# tempSensorCR2032.net
KiCad netlist of a schematic drawn in EAGLE
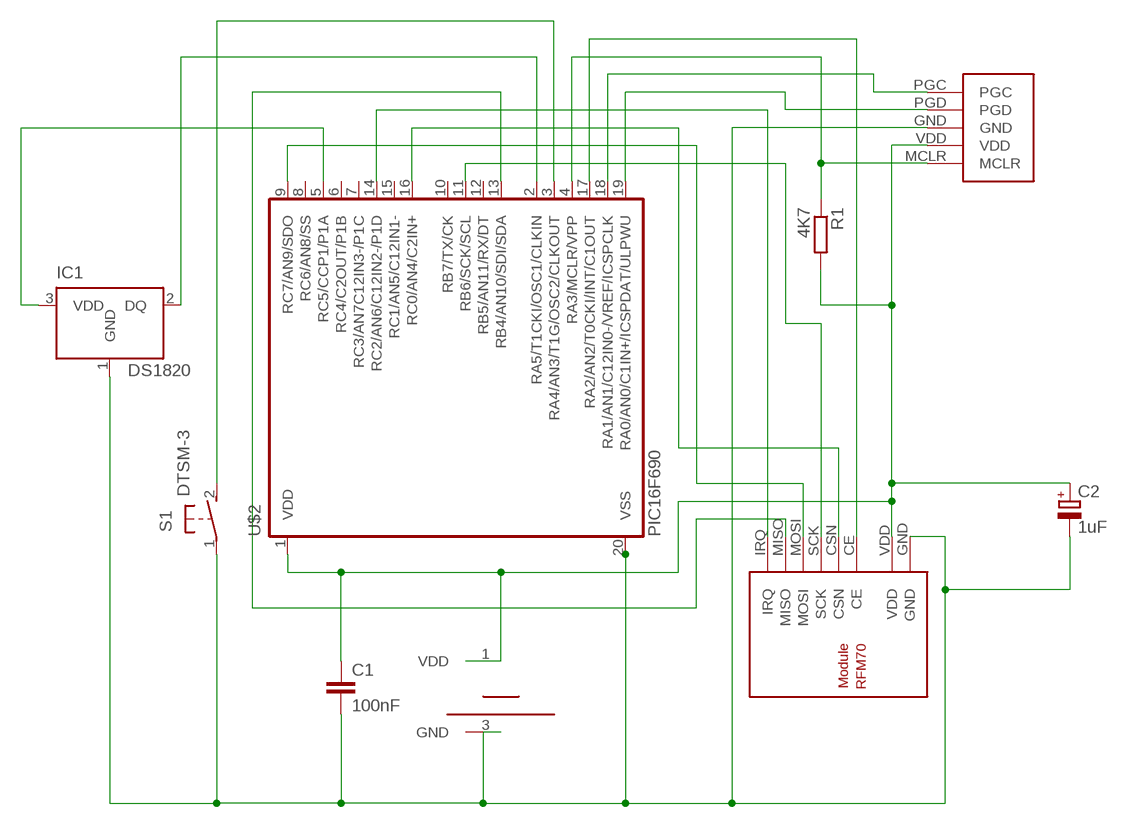
[diagram p0: schematic, sheet 1]

(export (version "E")
  (design (tool "Eeschema 10.0.6"))
  (components
    (comp (ref "C1")
      (value "100nF")
      (footprint "eagle-import:C2012")
      (libsource (lib "eagle-import") (part "C-EUC2012"))
    )
    (comp (ref "C2")
      (value "1uF")
      (footprint "eagle-import:SMC_A")
      (libsource (lib "eagle-import") (part "CPOL-EUSMCA"))
    )
    (comp (ref "IC1")
      (value "DS1820")
      (footprint "eagle-import:TO-92")
      (libsource (lib "eagle-import") (part "DS1820"))
    )
    (comp (ref "R1")
      (value "4K7")
      (footprint "eagle-import:R1206W")
      (libsource (lib "eagle-import") (part "R-EU_R1206W"))
    )
    (comp (ref "S1")
      (value "DTSM-3")
      (footprint "eagle-import:DTSM-3")
      (libsource (lib "eagle-import") (part "DTSM-3"))
    )
    (comp (ref "U$1")
      (value "RFM70")
      (footprint "eagle-import:RFM70")
      (libsource (lib "eagle-import") (part "RFM70"))
    )
    (comp (ref "U$2")
      (value "PIC16F690")
      (footprint "eagle-import:SSOP20")
      (libsource (lib "eagle-import") (part "PIC16F690"))
    )
    (comp (ref "U$3")
      (value "PROGRAMMINGHEADERDIP")
      (footprint "eagle-import:PROGHEADER")
      (libsource (lib "eagle-import") (part "PROGRAMMINGHEADERDIP"))
    )
    (comp (ref "U$4")
      (value "CR2032")
      (footprint "eagle-import:CR2032")
      (libsource (lib "eagle-import") (part "CR2032"))
    )
  )
  (nets
    (net (code "1") (name "Net-(IC1-DQ)") (class "Default")
      (node (ref "IC1") (pin "2") (pinfunction "DQ_2") (pintype "output"))
      (node (ref "U$2") (pin "2") (pinfunction "RA5/T1CKI/OSC1/CLKIN_2") (pintype "bidirectional"))
    )
    (net (code "2") (name "Net-(IC1-GND)") (class "Default")
      (node (ref "C1") (pin "2") (pinfunction "2_2") (pintype "passive"))
      (node (ref "C2") (pin "-") (pinfunction "-_-") (pintype "passive"))
      (node (ref "IC1") (pin "1") (pinfunction "GND_1") (pintype "power_in"))
      (node (ref "S1") (pin "1") (pinfunction "1_1") (pintype "passive"))
      (node (ref "U$1") (pin "GND") (pinfunction "GND_GND") (pintype "power_in"))
      (node (ref "U$2") (pin "20") (pinfunction "VSS_20") (pintype "power_in"))
      (node (ref "U$3") (pin "GND") (pinfunction "GND_GND") (pintype "power_in"))
      (node (ref "U$4") (pin "3") (pinfunction "GND_3") (pintype "bidirectional"))
    )
    (net (code "3") (name "Net-(IC1-VDD)") (class "Default")
      (node (ref "IC1") (pin "3") (pinfunction "VDD_3") (pintype "input"))
      (node (ref "U$2") (pin "5") (pinfunction "RC5/CCP1/P1A_5") (pintype "bidirectional"))
    )
    (net (code "4") (name "Net-(U$2-RA0{slash}AN0{slash}C1IN+{slash}ICSPDAT{slash}ULPWU)") (class "Default")
      (node (ref "U$2") (pin "19") (pinfunction "RA0/AN0/C1IN+/ICSPDAT/ULPWU_19") (pintype "bidirectional"))
      (node (ref "U$3") (pin "PGD") (pinfunction "PGD_PGD") (pintype "bidirectional"))
    )
    (net (code "5") (name "Net-(U$2-RA1{slash}AN1{slash}C12IN0-{slash}VREF{slash}ICSPCLK)") (class "Default")
      (node (ref "U$2") (pin "18") (pinfunction "RA1/AN1/C12IN0-/VREF/ICSPCLK_18") (pintype "bidirectional"))
      (node (ref "U$3") (pin "PGC") (pinfunction "PGC_PGC") (pintype "bidirectional"))
    )
    (net (code "6") (name "Net-(U$2-RA2{slash}AN2{slash}T0CKI{slash}INT{slash}C1OUT)") (class "Default")
      (node (ref "U$1") (pin "CE") (pinfunction "CE_CE") (pintype "bidirectional"))
      (node (ref "U$2") (pin "17") (pinfunction "RA2/AN2/T0CKI/INT/C1OUT_17") (pintype "bidirectional"))
    )
    (net (code "7") (name "Net-(U$2-RA3{slash}MCLR{slash}VPP)") (class "Default")
      (node (ref "R1") (pin "1") (pinfunction "1_1") (pintype "passive"))
      (node (ref "U$2") (pin "4") (pinfunction "RA3/MCLR/VPP_4") (pintype "bidirectional"))
      (node (ref "U$3") (pin "MCLR") (pinfunction "MCLR_MCLR") (pintype "output"))
    )
    (net (code "8") (name "Net-(U$2-RA4{slash}AN3{slash}T1G{slash}OSC2{slash}CLKOUT)") (class "Default")
      (node (ref "S1") (pin "2") (pinfunction "2_2") (pintype "passive"))
      (node (ref "U$2") (pin "3") (pinfunction "RA4/AN3/T1G/OSC2/CLKOUT_3") (pintype "bidirectional"))
    )
    (net (code "9") (name "Net-(U$2-RB4{slash}AN10{slash}SDI{slash}SDA)") (class "Default")
      (node (ref "U$1") (pin "MISO") (pinfunction "MISO_MISO") (pintype "bidirectional"))
      (node (ref "U$2") (pin "13") (pinfunction "RB4/AN10/SDI/SDA_13") (pintype "bidirectional"))
    )
    (net (code "10") (name "Net-(U$2-RB6{slash}SCK{slash}SCL)") (class "Default")
      (node (ref "U$1") (pin "SCK") (pinfunction "SCK_SCK") (pintype "bidirectional"))
      (node (ref "U$2") (pin "11") (pinfunction "RB6/SCK/SCL_11") (pintype "bidirectional"))
    )
    (net (code "11") (name "Net-(U$2-RC0{slash}AN4{slash}C2IN+)") (class "Default")
      (node (ref "U$1") (pin "CSN") (pinfunction "CSN_CSN") (pintype "bidirectional"))
      (node (ref "U$2") (pin "16") (pinfunction "RC0/AN4/C2IN+_16") (pintype "bidirectional"))
    )
    (net (code "12") (name "Net-(U$2-RC2{slash}AN6{slash}C12IN2-{slash}P1D)") (class "Default")
      (node (ref "U$1") (pin "IRQ") (pinfunction "IRQ_IRQ") (pintype "bidirectional"))
      (node (ref "U$2") (pin "14") (pinfunction "RC2/AN6/C12IN2-/P1D_14") (pintype "bidirectional"))
    )
    (net (code "13") (name "Net-(U$2-RC7{slash}AN9{slash}SDO)") (class "Default")
      (node (ref "U$1") (pin "MOSI") (pinfunction "MOSI_MOSI") (pintype "bidirectional"))
      (node (ref "U$2") (pin "9") (pinfunction "RC7/AN9/SDO_9") (pintype "bidirectional"))
    )
    (net (code "14") (name "Net-(U$2-VDD)") (class "Default")
      (node (ref "C1") (pin "1") (pinfunction "1_1") (pintype "passive"))
      (node (ref "C2") (pin "+") (pinfunction "+_+") (pintype "passive"))
      (node (ref "R1") (pin "2") (pinfunction "2_2") (pintype "passive"))
      (node (ref "U$1") (pin "VDD") (pinfunction "VDD_VDD") (pintype "power_in"))
      (node (ref "U$2") (pin "1") (pinfunction "VDD_1") (pintype "power_in"))
      (node (ref "U$3") (pin "VDD") (pinfunction "VDD_VDD") (pintype "power_in"))
      (node (ref "U$4") (pin "1") (pinfunction "VDD_1") (pintype "bidirectional"))
    )
    (net (code "15") (name "unconnected-(U$2-RB5{slash}AN11{slash}RX{slash}DT-Pad12)") (class "Default")
      (node (ref "U$2") (pin "12") (pinfunction "RB5/AN11/RX/DT_12") (pintype "bidirectional"))
    )
    (net (code "16") (name "unconnected-(U$2-RB7{slash}TX{slash}CK-Pad10)") (class "Default")
      (node (ref "U$2") (pin "10") (pinfunction "RB7/TX/CK_10") (pintype "bidirectional"))
    )
    (net (code "17") (name "unconnected-(U$2-RC1{slash}AN5{slash}C12IN1--Pad15)") (class "Default")
      (node (ref "U$2") (pin "15") (pinfunction "RC1/AN5/C12IN1-_15") (pintype "bidirectional"))
    )
    (net (code "18") (name "unconnected-(U$2-RC3{slash}AN7C12IN3-{slash}P1C-Pad7)") (class "Default")
      (node (ref "U$2") (pin "7") (pinfunction "RC3/AN7C12IN3-/P1C_7") (pintype "bidirectional"))
    )
    (net (code "19") (name "unconnected-(U$2-RC4{slash}C2OUT{slash}P1B-Pad6)") (class "Default")
      (node (ref "U$2") (pin "6") (pinfunction "RC4/C2OUT/P1B_6") (pintype "bidirectional"))
    )
    (net (code "20") (name "unconnected-(U$2-RC6{slash}AN8{slash}SS-Pad8)") (class "Default")
      (node (ref "U$2") (pin "8") (pinfunction "RC6/AN8/SS_8") (pintype "bidirectional"))
    )
  )
)
